# MAC_PHY_shield_boardrouter.net
KiCad netlist of a schematic drawn in EAGLE
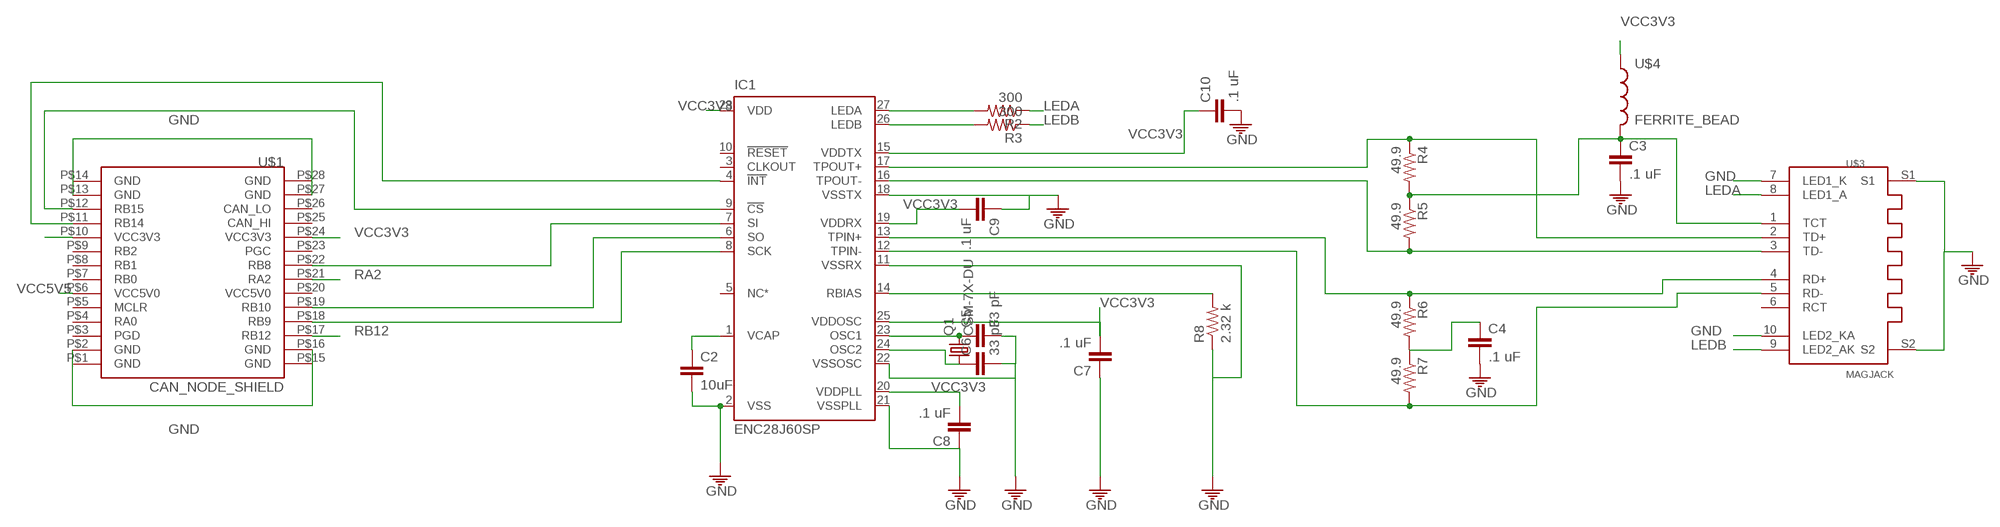
[diagram p0: schematic, sheet 1]

(export (version "E")
  (design (tool "Eeschema 10.0.6"))
  (components
    (comp (ref "C2")
      (value "10uF")
      (footprint "eagle-import:1206")
      (libsource (lib "eagle-import") (part "CAP1206"))
    )
    (comp (ref "C3")
      (value ".1 uF")
      (footprint "eagle-import:1206")
      (libsource (lib "eagle-import") (part "CAP1206"))
    )
    (comp (ref "C4")
      (value ".1 uF")
      (footprint "eagle-import:1206")
      (libsource (lib "eagle-import") (part "CAP1206"))
    )
    (comp (ref "C5")
      (value "33 pF")
      (footprint "eagle-import:1206")
      (libsource (lib "eagle-import") (part "CAP1206"))
    )
    (comp (ref "C6")
      (value "33 pF")
      (footprint "eagle-import:1206")
      (libsource (lib "eagle-import") (part "CAP1206"))
    )
    (comp (ref "C7")
      (value ".1 uF")
      (footprint "eagle-import:1206")
      (libsource (lib "eagle-import") (part "CAP1206"))
    )
    (comp (ref "C8")
      (value ".1 uF")
      (footprint "eagle-import:1206")
      (libsource (lib "eagle-import") (part "CAP1206"))
    )
    (comp (ref "C9")
      (value ".1 uF")
      (footprint "eagle-import:1206")
      (libsource (lib "eagle-import") (part "CAP1206"))
    )
    (comp (ref "C10")
      (value ".1 uF")
      (footprint "eagle-import:1206")
      (libsource (lib "eagle-import") (part "CAP1206"))
    )
    (comp (ref "IC1")
      (value "ENC28J60SP")
      (footprint "eagle-import:DIL28-3")
      (fields (field (name "MF") "MICROCHIP") (field (name "MPN") "ENC28J60/SP"))
      (libsource (lib "eagle-import") (part "ENC28J60SP"))
    )
    (comp (ref "Q1")
      (value "CSM-7X-DU")
      (footprint "eagle-import:CSM-7X-DU")
      (libsource (lib "eagle-import") (part "CSM-7X-DU"))
    )
    (comp (ref "R2")
      (value "300")
      (footprint "eagle-import:0805")
      (libsource (lib "eagle-import") (part "RESISTOR0805-RES"))
    )
    (comp (ref "R3")
      (value "300")
      (footprint "eagle-import:0805")
      (libsource (lib "eagle-import") (part "RESISTOR0805-RES"))
    )
    (comp (ref "R4")
      (value "49.9")
      (footprint "eagle-import:0805")
      (libsource (lib "eagle-import") (part "RESISTOR0805-RES"))
    )
    (comp (ref "R5")
      (value "49.9")
      (footprint "eagle-import:0805")
      (libsource (lib "eagle-import") (part "RESISTOR0805-RES"))
    )
    (comp (ref "R6")
      (value "49.9")
      (footprint "eagle-import:0805")
      (libsource (lib "eagle-import") (part "RESISTOR0805-RES"))
    )
    (comp (ref "R7")
      (value "49.9")
      (footprint "eagle-import:0805")
      (libsource (lib "eagle-import") (part "RESISTOR0805-RES"))
    )
    (comp (ref "R8")
      (value "2.32 k")
      (footprint "eagle-import:0805")
      (libsource (lib "eagle-import") (part "RESISTOR0805-RES"))
    )
    (comp (ref "U$1")
      (value "CAN_NODE_SHIELD")
      (footprint "eagle-import:CAN_NODE_SHIELD")
      (libsource (lib "eagle-import") (part "CAN_NODE_SHIELD"))
    )
    (comp (ref "U$3")
      (value "MAGJACK")
      (footprint "eagle-import:08B0-1X1T-06-F")
      (libsource (lib "eagle-import") (part "MAGJACK"))
    )
    (comp (ref "U$4")
      (value "FERRITE_BEAD")
      (footprint "eagle-import:1206")
      (libsource (lib "eagle-import") (part "FERRITE_BEAD"))
    )
  )
  (nets
    (net (code "1") (name "/LEDA") (class "Default")
      (node (ref "R2") (pin "1") (pinfunction "1_1") (pintype "passive"))
      (node (ref "U$3") (pin "8") (pinfunction "LED1_A_8") (pintype "bidirectional"))
    )
    (net (code "2") (name "/LEDB") (class "Default")
      (node (ref "R3") (pin "1") (pinfunction "1_1") (pintype "passive"))
      (node (ref "U$3") (pin "9") (pinfunction "LED2_AK_9") (pintype "bidirectional"))
    )
    (net (code "3") (name "/RA2") (class "Default")
      (node (ref "U$1") (pin "P$21") (pinfunction "RA2_P$21") (pintype "bidirectional"))
    )
    (net (code "4") (name "/RB12") (class "Default")
      (node (ref "U$1") (pin "P$17") (pinfunction "RB12_P$17") (pintype "bidirectional"))
    )
    (net (code "5") (name "/VCC3V3") (class "Default")
      (node (ref "C10") (pin "1") (pinfunction "1_1") (pintype "passive"))
      (node (ref "C7") (pin "2") (pinfunction "2_2") (pintype "passive"))
      (node (ref "C8") (pin "2") (pinfunction "2_2") (pintype "passive"))
      (node (ref "C9") (pin "2") (pinfunction "2_2") (pintype "passive"))
      (node (ref "IC1") (pin "15") (pinfunction "VDDTX_15") (pintype "input"))
      (node (ref "IC1") (pin "19") (pinfunction "VDDRX_19") (pintype "input"))
      (node (ref "IC1") (pin "20") (pinfunction "VDDPLL_20") (pintype "input"))
      (node (ref "IC1") (pin "25") (pinfunction "VDDOSC_25") (pintype "input"))
      (node (ref "IC1") (pin "28") (pinfunction "VDD_28") (pintype "input"))
      (node (ref "U$1") (pin "P$10") (pinfunction "VCC3V3_P$10") (pintype "bidirectional"))
      (node (ref "U$1") (pin "P$24") (pinfunction "VCC3V3_P$24") (pintype "bidirectional"))
      (node (ref "U$4") (pin "1") (pinfunction "1_1") (pintype "passive"))
    )
    (net (code "6") (name "/VCC5V5") (class "Default")
      (node (ref "U$1") (pin "P$6") (pinfunction "VCC5V0_P$6") (pintype "bidirectional"))
    )
    (net (code "7") (name "GND") (class "Default")
      (node (ref "C10") (pin "2") (pinfunction "2_2") (pintype "passive"))
      (node (ref "C2") (pin "2") (pinfunction "2_2") (pintype "passive"))
      (node (ref "C3") (pin "2") (pinfunction "2_2") (pintype "passive"))
      (node (ref "C4") (pin "2") (pinfunction "2_2") (pintype "passive"))
      (node (ref "C5") (pin "2") (pinfunction "2_2") (pintype "passive"))
      (node (ref "C6") (pin "2") (pinfunction "2_2") (pintype "passive"))
      (node (ref "C7") (pin "1") (pinfunction "1_1") (pintype "passive"))
      (node (ref "C8") (pin "1") (pinfunction "1_1") (pintype "passive"))
      (node (ref "C9") (pin "1") (pinfunction "1_1") (pintype "passive"))
      (node (ref "IC1") (pin "11") (pinfunction "VSSRX_11") (pintype "input"))
      (node (ref "IC1") (pin "18") (pinfunction "VSSTX_18") (pintype "input"))
      (node (ref "IC1") (pin "2") (pinfunction "VSS_2") (pintype "input"))
      (node (ref "IC1") (pin "21") (pinfunction "VSSPLL_21") (pintype "input"))
      (node (ref "IC1") (pin "22") (pinfunction "VSSOSC_22") (pintype "input"))
      (node (ref "R8") (pin "1") (pinfunction "1_1") (pintype "passive"))
      (node (ref "U$1") (pin "P$1") (pinfunction "GND_P$1") (pintype "bidirectional"))
      (node (ref "U$1") (pin "P$13") (pinfunction "GND_P$13") (pintype "bidirectional"))
      (node (ref "U$1") (pin "P$14") (pinfunction "GND_P$14") (pintype "bidirectional"))
      (node (ref "U$1") (pin "P$15") (pinfunction "GND_P$15") (pintype "bidirectional"))
      (node (ref "U$1") (pin "P$16") (pinfunction "GND_P$16") (pintype "bidirectional"))
      (node (ref "U$1") (pin "P$2") (pinfunction "GND_P$2") (pintype "bidirectional"))
      (node (ref "U$1") (pin "P$27") (pinfunction "GND_P$27") (pintype "bidirectional"))
      (node (ref "U$1") (pin "P$28") (pinfunction "GND_P$28") (pintype "bidirectional"))
      (node (ref "U$3") (pin "10") (pinfunction "LED2_KA_10") (pintype "bidirectional"))
      (node (ref "U$3") (pin "7") (pinfunction "LED1_K_7") (pintype "bidirectional"))
      (node (ref "U$3") (pin "S1") (pinfunction "S1_S1") (pintype "bidirectional"))
      (node (ref "U$3") (pin "S2") (pinfunction "S2_S2") (pintype "bidirectional"))
    )
    (net (code "8") (name "Net-(C4-Pad1)") (class "Default")
      (node (ref "C4") (pin "1") (pinfunction "1_1") (pintype "passive"))
      (node (ref "R6") (pin "2") (pinfunction "2_2") (pintype "passive"))
      (node (ref "R7") (pin "1") (pinfunction "1_1") (pintype "passive"))
    )
    (net (code "9") (name "Net-(IC1-LEDA)") (class "Default")
      (node (ref "IC1") (pin "27") (pinfunction "LEDA_27") (pintype "output"))
      (node (ref "R2") (pin "2") (pinfunction "2_2") (pintype "passive"))
    )
    (net (code "10") (name "Net-(IC1-LEDB)") (class "Default")
      (node (ref "IC1") (pin "26") (pinfunction "LEDB_26") (pintype "output"))
      (node (ref "R3") (pin "2") (pinfunction "2_2") (pintype "passive"))
    )
    (net (code "11") (name "Net-(IC1-OSC1)") (class "Default")
      (node (ref "C5") (pin "1") (pinfunction "1_1") (pintype "passive"))
      (node (ref "IC1") (pin "23") (pinfunction "OSC1_23") (pintype "input"))
      (node (ref "Q1") (pin "2") (pinfunction "2_2") (pintype "passive"))
    )
    (net (code "12") (name "Net-(IC1-OSC2)") (class "Default")
      (node (ref "C6") (pin "1") (pinfunction "1_1") (pintype "passive"))
      (node (ref "IC1") (pin "24") (pinfunction "OSC2_24") (pintype "output"))
      (node (ref "Q1") (pin "1") (pinfunction "1_1") (pintype "passive"))
    )
    (net (code "13") (name "Net-(IC1-RBIAS)") (class "Default")
      (node (ref "IC1") (pin "14") (pinfunction "RBIAS_14") (pintype "input"))
      (node (ref "R8") (pin "2") (pinfunction "2_2") (pintype "passive"))
    )
    (net (code "14") (name "Net-(IC1-SCK)") (class "Default")
      (node (ref "IC1") (pin "8") (pinfunction "SCK_8") (pintype "input"))
      (node (ref "U$1") (pin "P$18") (pinfunction "RB9_P$18") (pintype "bidirectional"))
    )
    (net (code "15") (name "Net-(IC1-SI)") (class "Default")
      (node (ref "IC1") (pin "7") (pinfunction "SI_7") (pintype "input"))
      (node (ref "U$1") (pin "P$22") (pinfunction "RB8_P$22") (pintype "bidirectional"))
    )
    (net (code "16") (name "Net-(IC1-SO)") (class "Default")
      (node (ref "IC1") (pin "6") (pinfunction "SO_6") (pintype "output"))
      (node (ref "U$1") (pin "P$19") (pinfunction "RB10_P$19") (pintype "bidirectional"))
    )
    (net (code "17") (name "Net-(IC1-TPIN+)") (class "Default")
      (node (ref "IC1") (pin "13") (pinfunction "TPIN+_13") (pintype "input"))
      (node (ref "R6") (pin "1") (pinfunction "1_1") (pintype "passive"))
      (node (ref "U$3") (pin "4") (pinfunction "RD+_4") (pintype "bidirectional"))
    )
    (net (code "18") (name "Net-(IC1-TPIN-)") (class "Default")
      (node (ref "IC1") (pin "12") (pinfunction "TPIN-_12") (pintype "input"))
      (node (ref "R7") (pin "2") (pinfunction "2_2") (pintype "passive"))
      (node (ref "U$3") (pin "5") (pinfunction "RD-_5") (pintype "bidirectional"))
    )
    (net (code "19") (name "Net-(IC1-TPOUT+)") (class "Default")
      (node (ref "IC1") (pin "17") (pinfunction "TPOUT+_17") (pintype "output"))
      (node (ref "R4") (pin "1") (pinfunction "1_1") (pintype "passive"))
      (node (ref "U$3") (pin "2") (pinfunction "TD+_2") (pintype "bidirectional"))
    )
    (net (code "20") (name "Net-(IC1-TPOUT-)") (class "Default")
      (node (ref "IC1") (pin "16") (pinfunction "TPOUT-_16") (pintype "output"))
      (node (ref "R5") (pin "2") (pinfunction "2_2") (pintype "passive"))
      (node (ref "U$3") (pin "3") (pinfunction "TD-_3") (pintype "bidirectional"))
    )
    (net (code "21") (name "Net-(IC1-VCAP)") (class "Default")
      (node (ref "C2") (pin "1") (pinfunction "1_1") (pintype "passive"))
      (node (ref "IC1") (pin "1") (pinfunction "VCAP_1") (pintype "input"))
    )
    (net (code "22") (name "Net-(IC1-~{CS})") (class "Default")
      (node (ref "IC1") (pin "9") (pinfunction "~{CS}_9") (pintype "input"))
      (node (ref "U$1") (pin "P$12") (pinfunction "RB15_P$12") (pintype "bidirectional"))
    )
    (net (code "23") (name "Net-(IC1-~{INT})") (class "Default")
      (node (ref "IC1") (pin "4") (pinfunction "~{INT}_4") (pintype "output"))
      (node (ref "U$1") (pin "P$11") (pinfunction "RB14_P$11") (pintype "bidirectional"))
    )
    (net (code "24") (name "Net-(U$3-TCT)") (class "Default")
      (node (ref "C3") (pin "1") (pinfunction "1_1") (pintype "passive"))
      (node (ref "R4") (pin "2") (pinfunction "2_2") (pintype "passive"))
      (node (ref "R5") (pin "1") (pinfunction "1_1") (pintype "passive"))
      (node (ref "U$3") (pin "1") (pinfunction "TCT_1") (pintype "bidirectional"))
      (node (ref "U$4") (pin "2") (pinfunction "2_2") (pintype "passive"))
    )
    (net (code "25") (name "unconnected-(IC1-CLKOUT-Pad3)") (class "Default")
      (node (ref "IC1") (pin "3") (pinfunction "CLKOUT_3") (pintype "output"))
    )
    (net (code "26") (name "unconnected-(IC1-NC*-Pad5)") (class "Default")
      (node (ref "IC1") (pin "5") (pinfunction "NC*_5") (pintype "output"))
    )
    (net (code "27") (name "unconnected-(IC1-~{RESET}-Pad10)") (class "Default")
      (node (ref "IC1") (pin "10") (pinfunction "~{RESET}_10") (pintype "input"))
    )
    (net (code "28") (name "unconnected-(U$1-CAN_HI-PadP$25)") (class "Default")
      (node (ref "U$1") (pin "P$25") (pinfunction "CAN_HI_P$25") (pintype "bidirectional"))
    )
    (net (code "29") (name "unconnected-(U$1-CAN_LO-PadP$26)") (class "Default")
      (node (ref "U$1") (pin "P$26") (pinfunction "CAN_LO_P$26") (pintype "bidirectional"))
    )
    (net (code "30") (name "unconnected-(U$1-MCLR-PadP$5)") (class "Default")
      (node (ref "U$1") (pin "P$5") (pinfunction "MCLR_P$5") (pintype "bidirectional"))
    )
    (net (code "31") (name "unconnected-(U$1-PGC-PadP$23)") (class "Default")
      (node (ref "U$1") (pin "P$23") (pinfunction "PGC_P$23") (pintype "bidirectional"))
    )
    (net (code "32") (name "unconnected-(U$1-PGD-PadP$3)") (class "Default")
      (node (ref "U$1") (pin "P$3") (pinfunction "PGD_P$3") (pintype "bidirectional"))
    )
    (net (code "33") (name "unconnected-(U$1-RA0-PadP$4)") (class "Default")
      (node (ref "U$1") (pin "P$4") (pinfunction "RA0_P$4") (pintype "bidirectional"))
    )
    (net (code "34") (name "unconnected-(U$1-RB0-PadP$7)") (class "Default")
      (node (ref "U$1") (pin "P$7") (pinfunction "RB0_P$7") (pintype "bidirectional"))
    )
    (net (code "35") (name "unconnected-(U$1-RB1-PadP$8)") (class "Default")
      (node (ref "U$1") (pin "P$8") (pinfunction "RB1_P$8") (pintype "bidirectional"))
    )
    (net (code "36") (name "unconnected-(U$1-RB2-PadP$9)") (class "Default")
      (node (ref "U$1") (pin "P$9") (pinfunction "RB2_P$9") (pintype "bidirectional"))
    )
    (net (code "37") (name "unconnected-(U$1-VCC5V0-PadP$20)") (class "Default")
      (node (ref "U$1") (pin "P$20") (pinfunction "VCC5V0_P$20") (pintype "bidirectional"))
    )
    (net (code "38") (name "unconnected-(U$3-RCT-Pad6)") (class "Default")
      (node (ref "U$3") (pin "6") (pinfunction "RCT_6") (pintype "bidirectional"))
    )
  )
)
